# SCH_EVTY_2024-05-09.net
KiCad netlist of a schematic drawn in EasyEDA
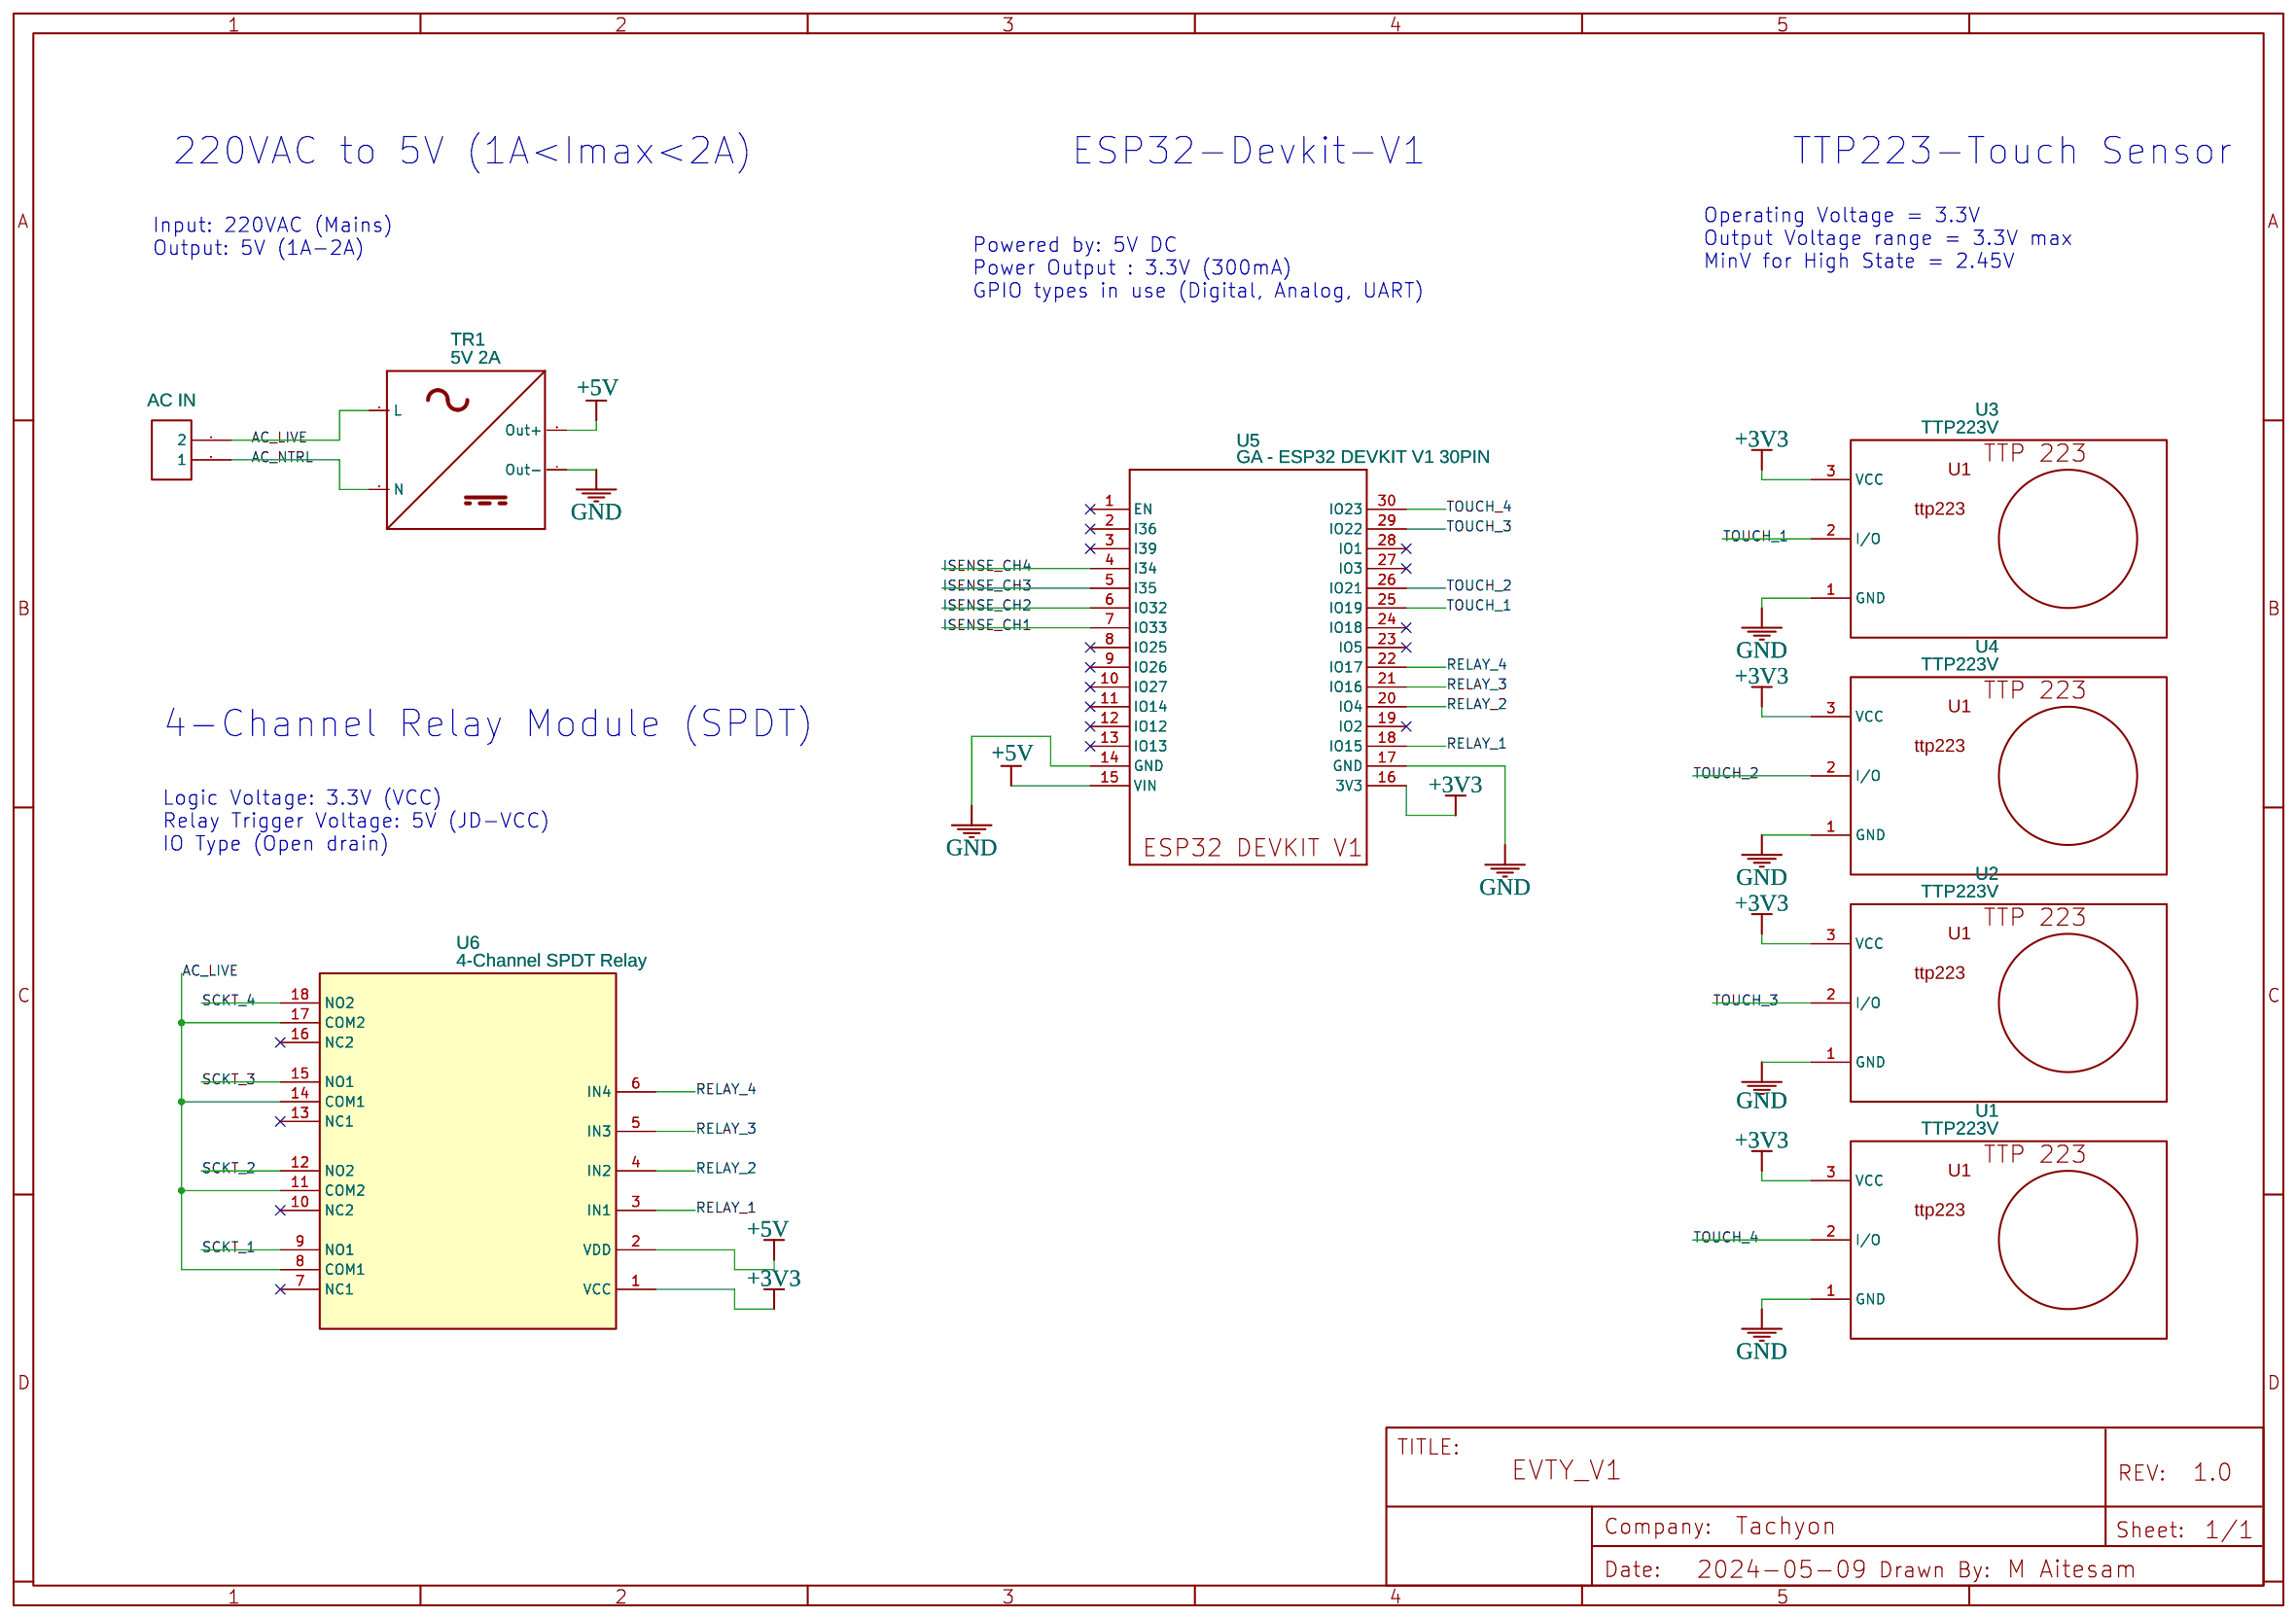
[diagram p0: schematic sheet]

(export (version "E")
  (design (tool "Eeschema 10.0.6"))
  (components
    (comp (ref "OUT1")
      (value "AC IN")
      (fields (field (name "Manufacturer Part") "RELIMATE CON 3 PIN"))
      (libsource (lib "") (part "2_pin_RELIMATE"))
    )
    (comp (ref "TR1") (value "5V 2A") (libsource (lib "") (part "AC_DC_adapter")))
    (comp (ref "U1") (value "TTP223V") (libsource (lib "") (part "TTP223V")))
    (comp (ref "U2") (value "TTP223V") (libsource (lib "") (part "TTP223V")))
    (comp (ref "U3") (value "TTP223V") (libsource (lib "") (part "TTP223V")))
    (comp (ref "U4") (value "TTP223V") (libsource (lib "") (part "TTP223V")))
    (comp (ref "U5") (value "GA - ESP32 DEVKIT V1 30PIN") (libsource (lib "") (part "ESP32-DEVKIT-V1-30PIN")))
    (comp (ref "U6")
      (value "4-Channel SPDT Relay")
      (fields (field (name "Manufacturer Part") "MF-6402393") (field (name "Manufacturer") "MAKERFACTORY"))
      (libsource (lib "") (part "Basic 4-Channel SPDT Relay Carrier with 5VDC Relays"))
    )
  )
  (nets
    (net (code "1") (name "+3V3") (class "Default")
      (node (ref "U1") (pin "3") (pinfunction "VCC_3") (pintype "unspecified"))
      (node (ref "U2") (pin "3") (pinfunction "VCC_3") (pintype "unspecified"))
      (node (ref "U3") (pin "3") (pinfunction "VCC_3") (pintype "unspecified"))
      (node (ref "U4") (pin "3") (pinfunction "VCC_3") (pintype "unspecified"))
      (node (ref "U5") (pin "16") (pinfunction "3V3_16") (pintype "unspecified"))
      (node (ref "U6") (pin "1") (pinfunction "VCC_1") (pintype "unspecified"))
    )
    (net (code "2") (name "+5V") (class "Default")
      (node (ref "TR1") (pin "3") (pinfunction "Out+_3") (pintype "unspecified"))
      (node (ref "U5") (pin "15") (pinfunction "VIN_15") (pintype "unspecified"))
      (node (ref "U6") (pin "2") (pinfunction "VDD_2") (pintype "unspecified"))
    )
    (net (code "3") (name "/AC_LIVE") (class "Default")
      (node (ref "OUT1") (pin "2") (pinfunction "2_2") (pintype "unspecified"))
      (node (ref "TR1") (pin "1") (pinfunction "L_1") (pintype "unspecified"))
      (node (ref "U6") (pin "11") (pinfunction "COM2_11") (pintype "unspecified"))
      (node (ref "U6") (pin "14") (pinfunction "COM1_14") (pintype "unspecified"))
      (node (ref "U6") (pin "17") (pinfunction "COM2_17") (pintype "unspecified"))
      (node (ref "U6") (pin "8") (pinfunction "COM1_8") (pintype "unspecified"))
    )
    (net (code "4") (name "/AC_NTRL") (class "Default")
      (node (ref "OUT1") (pin "1") (pinfunction "1_1") (pintype "unspecified"))
      (node (ref "TR1") (pin "2") (pinfunction "N_2") (pintype "unspecified"))
    )
    (net (code "5") (name "/ISENSE_CH1") (class "Default")
      (node (ref "U5") (pin "7") (pinfunction "IO33_7") (pintype "unspecified"))
    )
    (net (code "6") (name "/ISENSE_CH2") (class "Default")
      (node (ref "U5") (pin "6") (pinfunction "IO32_6") (pintype "unspecified"))
    )
    (net (code "7") (name "/ISENSE_CH3") (class "Default")
      (node (ref "U5") (pin "5") (pinfunction "I35_5") (pintype "unspecified"))
    )
    (net (code "8") (name "/ISENSE_CH4") (class "Default")
      (node (ref "U5") (pin "4") (pinfunction "I34_4") (pintype "unspecified"))
    )
    (net (code "9") (name "/RELAY_1") (class "Default")
      (node (ref "U5") (pin "18") (pinfunction "IO15_18") (pintype "unspecified"))
      (node (ref "U6") (pin "3") (pinfunction "IN1_3") (pintype "unspecified"))
    )
    (net (code "10") (name "/RELAY_2") (class "Default")
      (node (ref "U5") (pin "20") (pinfunction "IO4_20") (pintype "unspecified"))
      (node (ref "U6") (pin "4") (pinfunction "IN2_4") (pintype "unspecified"))
    )
    (net (code "11") (name "/RELAY_3") (class "Default")
      (node (ref "U5") (pin "21") (pinfunction "IO16_21") (pintype "unspecified"))
      (node (ref "U6") (pin "5") (pinfunction "IN3_5") (pintype "unspecified"))
    )
    (net (code "12") (name "/RELAY_4") (class "Default")
      (node (ref "U5") (pin "22") (pinfunction "IO17_22") (pintype "unspecified"))
      (node (ref "U6") (pin "6") (pinfunction "IN4_6") (pintype "unspecified"))
    )
    (net (code "13") (name "/SCKT_1") (class "Default")
      (node (ref "U6") (pin "9") (pinfunction "NO1_9") (pintype "unspecified"))
    )
    (net (code "14") (name "/SCKT_2") (class "Default")
      (node (ref "U6") (pin "12") (pinfunction "NO2_12") (pintype "unspecified"))
    )
    (net (code "15") (name "/SCKT_3") (class "Default")
      (node (ref "U6") (pin "15") (pinfunction "NO1_15") (pintype "unspecified"))
    )
    (net (code "16") (name "/SCKT_4") (class "Default")
      (node (ref "U6") (pin "18") (pinfunction "NO2_18") (pintype "unspecified"))
    )
    (net (code "17") (name "/TOUCH_1") (class "Default")
      (node (ref "U3") (pin "2") (pinfunction "I/O_2") (pintype "unspecified"))
      (node (ref "U5") (pin "25") (pinfunction "IO19_25") (pintype "unspecified"))
    )
    (net (code "18") (name "/TOUCH_2") (class "Default")
      (node (ref "U4") (pin "2") (pinfunction "I/O_2") (pintype "unspecified"))
      (node (ref "U5") (pin "26") (pinfunction "IO21_26") (pintype "unspecified"))
    )
    (net (code "19") (name "/TOUCH_3") (class "Default")
      (node (ref "U2") (pin "2") (pinfunction "I/O_2") (pintype "unspecified"))
      (node (ref "U5") (pin "29") (pinfunction "IO22_29") (pintype "unspecified"))
    )
    (net (code "20") (name "/TOUCH_4") (class "Default")
      (node (ref "U1") (pin "2") (pinfunction "I/O_2") (pintype "unspecified"))
      (node (ref "U5") (pin "30") (pinfunction "IO23_30") (pintype "unspecified"))
    )
    (net (code "21") (name "GND") (class "Default")
      (node (ref "TR1") (pin "4") (pinfunction "Out-_4") (pintype "unspecified"))
      (node (ref "U1") (pin "1") (pinfunction "GND_1") (pintype "unspecified"))
      (node (ref "U2") (pin "1") (pinfunction "GND_1") (pintype "unspecified"))
      (node (ref "U3") (pin "1") (pinfunction "GND_1") (pintype "unspecified"))
      (node (ref "U4") (pin "1") (pinfunction "GND_1") (pintype "unspecified"))
      (node (ref "U5") (pin "14") (pinfunction "GND_14") (pintype "unspecified"))
      (node (ref "U5") (pin "17") (pinfunction "GND_17") (pintype "unspecified"))
    )
    (net (code "22") (name "unconnected-(U5-EN-Pad1)") (class "Default")
      (node (ref "U5") (pin "1") (pinfunction "EN_1") (pintype "unspecified+no_connect"))
    )
    (net (code "23") (name "unconnected-(U5-I36-Pad2)") (class "Default")
      (node (ref "U5") (pin "2") (pinfunction "I36_2") (pintype "unspecified+no_connect"))
    )
    (net (code "24") (name "unconnected-(U5-I39-Pad3)") (class "Default")
      (node (ref "U5") (pin "3") (pinfunction "I39_3") (pintype "unspecified+no_connect"))
    )
    (net (code "25") (name "unconnected-(U5-IO1-Pad28)") (class "Default")
      (node (ref "U5") (pin "28") (pinfunction "IO1_28") (pintype "unspecified+no_connect"))
    )
    (net (code "26") (name "unconnected-(U5-IO2-Pad19)") (class "Default")
      (node (ref "U5") (pin "19") (pinfunction "IO2_19") (pintype "unspecified+no_connect"))
    )
    (net (code "27") (name "unconnected-(U5-IO3-Pad27)") (class "Default")
      (node (ref "U5") (pin "27") (pinfunction "IO3_27") (pintype "unspecified+no_connect"))
    )
    (net (code "28") (name "unconnected-(U5-IO5-Pad23)") (class "Default")
      (node (ref "U5") (pin "23") (pinfunction "IO5_23") (pintype "unspecified+no_connect"))
    )
    (net (code "29") (name "unconnected-(U5-IO12-Pad12)") (class "Default")
      (node (ref "U5") (pin "12") (pinfunction "IO12_12") (pintype "unspecified+no_connect"))
    )
    (net (code "30") (name "unconnected-(U5-IO13-Pad13)") (class "Default")
      (node (ref "U5") (pin "13") (pinfunction "IO13_13") (pintype "unspecified+no_connect"))
    )
    (net (code "31") (name "unconnected-(U5-IO14-Pad11)") (class "Default")
      (node (ref "U5") (pin "11") (pinfunction "IO14_11") (pintype "unspecified+no_connect"))
    )
    (net (code "32") (name "unconnected-(U5-IO18-Pad24)") (class "Default")
      (node (ref "U5") (pin "24") (pinfunction "IO18_24") (pintype "unspecified+no_connect"))
    )
    (net (code "33") (name "unconnected-(U5-IO25-Pad8)") (class "Default")
      (node (ref "U5") (pin "8") (pinfunction "IO25_8") (pintype "unspecified+no_connect"))
    )
    (net (code "34") (name "unconnected-(U5-IO26-Pad9)") (class "Default")
      (node (ref "U5") (pin "9") (pinfunction "IO26_9") (pintype "unspecified+no_connect"))
    )
    (net (code "35") (name "unconnected-(U5-IO27-Pad10)") (class "Default")
      (node (ref "U5") (pin "10") (pinfunction "IO27_10") (pintype "unspecified+no_connect"))
    )
    (net (code "36") (name "unconnected-(U6-NC1-Pad7)") (class "Default")
      (node (ref "U6") (pin "7") (pinfunction "NC1_7") (pintype "unspecified+no_connect"))
    )
    (net (code "37") (name "unconnected-(U6-NC1-Pad13)") (class "Default")
      (node (ref "U6") (pin "13") (pinfunction "NC1_13") (pintype "unspecified+no_connect"))
    )
    (net (code "38") (name "unconnected-(U6-NC2-Pad10)") (class "Default")
      (node (ref "U6") (pin "10") (pinfunction "NC2_10") (pintype "unspecified+no_connect"))
    )
    (net (code "39") (name "unconnected-(U6-NC2-Pad16)") (class "Default")
      (node (ref "U6") (pin "16") (pinfunction "NC2_16") (pintype "unspecified+no_connect"))
    )
  )
)
